# 5V_Isolator.net
KiCad netlist of a schematic drawn in Altium Designer
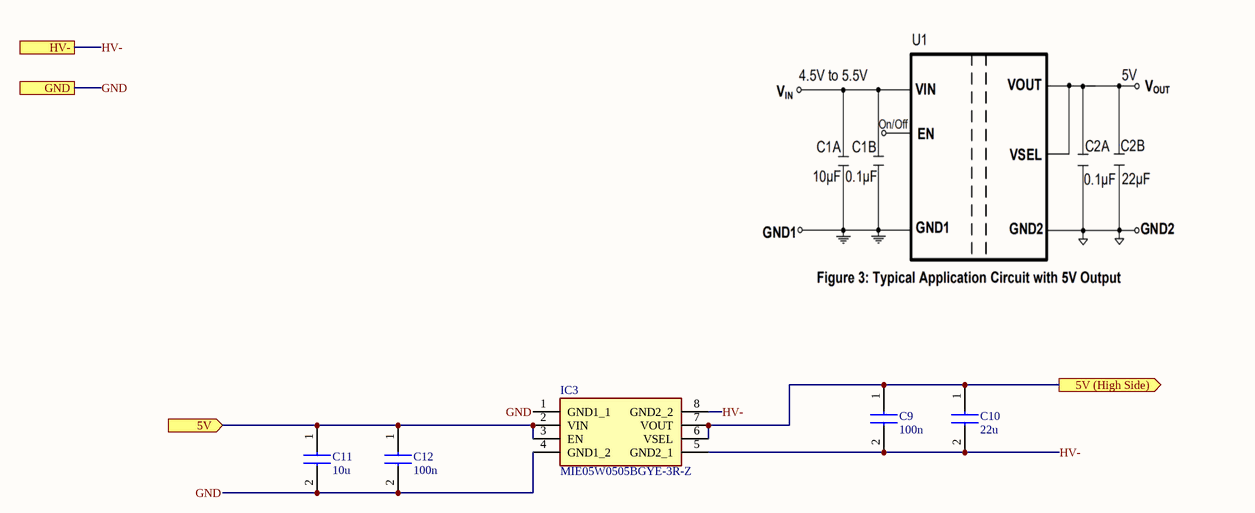
[diagram p0: 5V_Isolator.SchDoc]

(export (version "E")
  (design (tool "Eeschema 10.0.6"))
  (components
    (comp (ref "C9")
      (value "100n")
      (footprint "SamacSys:CAPC2012X147N")
      (description "Capacitor")
      (fields
        (field (name "MANUFACTURER_PART_NUMBER") "KGF21BR71H104KT")
        (field (name "MOUSER PART NUMBER") "581-KGF21BR71H104KT")
      )
      (libsource (lib "SamacSys") (part "KGF21BR71H104KT"))
    )
    (comp (ref "C10")
      (value "22u")
      (footprint "SamacSys:CAPC2012X145N")
      (description "Capacitor")
      (fields (field (name "MANUFACTURER_PART_NUMBER") "GXT21BR61C226ME13L"))
      (libsource (lib "SamacSys") (part "GXT21BR61C226ME13L"))
    )
    (comp (ref "C11")
      (value "10u")
      (footprint "SamacSys:GRM21BR60J226ME39L")
      (description "Capacitor")
      (fields
        (field (name "MANUFACTURER_PART_NUMBER") "GRM21BR61H106KE43L")
        (field (name "MOUSER PART NUMBER") "81-GRM21BR61H106KE3L")
      )
      (libsource (lib "SamacSys") (part "GRM21BR61H106KE43L"))
    )
    (comp (ref "C12")
      (value "100n")
      (footprint "SamacSys:CAPC2012X147N")
      (description "Capacitor")
      (fields
        (field (name "MANUFACTURER_PART_NUMBER") "KGF21BR71H104KT")
        (field (name "MOUSER PART NUMBER") "581-KGF21BR71H104KT")
      )
      (libsource (lib "SamacSys") (part "KGF21BR71H104KT"))
    )
    (comp (ref "IC3")
      (value "MIE05W0505BGYE-3R-Z")
      (footprint "SamacSys:SOIC127P1030X265-8N")
      (description "Integrated Circuit")
      (libsource (lib "SamacSys") (part "MIE05W0505BGYE-3R-Z"))
    )
  )
  (nets
    (net (code "1") (name "/5V") (class "Default")
      (node (ref "C11") (pin "1") (pinfunction "1_1") (pintype "passive"))
      (node (ref "C12") (pin "1") (pinfunction "1_1") (pintype "passive"))
      (node (ref "IC3") (pin "2") (pinfunction "VIN_2") (pintype "passive"))
      (node (ref "IC3") (pin "3") (pinfunction "EN_3") (pintype "passive"))
    )
    (net (code "2") (name "/5V (High Side)") (class "Default")
      (node (ref "C10") (pin "1") (pinfunction "1_1") (pintype "passive"))
      (node (ref "C9") (pin "1") (pinfunction "1_1") (pintype "passive"))
      (node (ref "IC3") (pin "6") (pinfunction "VSEL_6") (pintype "passive"))
      (node (ref "IC3") (pin "7") (pinfunction "VOUT_7") (pintype "passive"))
    )
    (net (code "3") (name "/GND") (class "Default")
      (node (ref "C11") (pin "2") (pinfunction "2_2") (pintype "passive"))
      (node (ref "C12") (pin "2") (pinfunction "2_2") (pintype "passive"))
      (node (ref "IC3") (pin "1") (pinfunction "GND1_1_1") (pintype "passive"))
      (node (ref "IC3") (pin "4") (pinfunction "GND1_2_4") (pintype "passive"))
    )
    (net (code "4") (name "/HV-") (class "Default")
      (node (ref "C10") (pin "2") (pinfunction "2_2") (pintype "passive"))
      (node (ref "C9") (pin "2") (pinfunction "2_2") (pintype "passive"))
      (node (ref "IC3") (pin "5") (pinfunction "GND2_1_5") (pintype "passive"))
      (node (ref "IC3") (pin "8") (pinfunction "GND2_2_8") (pintype "passive"))
    )
  )
)
